# Arm_controller.net
KiCad netlist of a schematic drawn in EAGLE
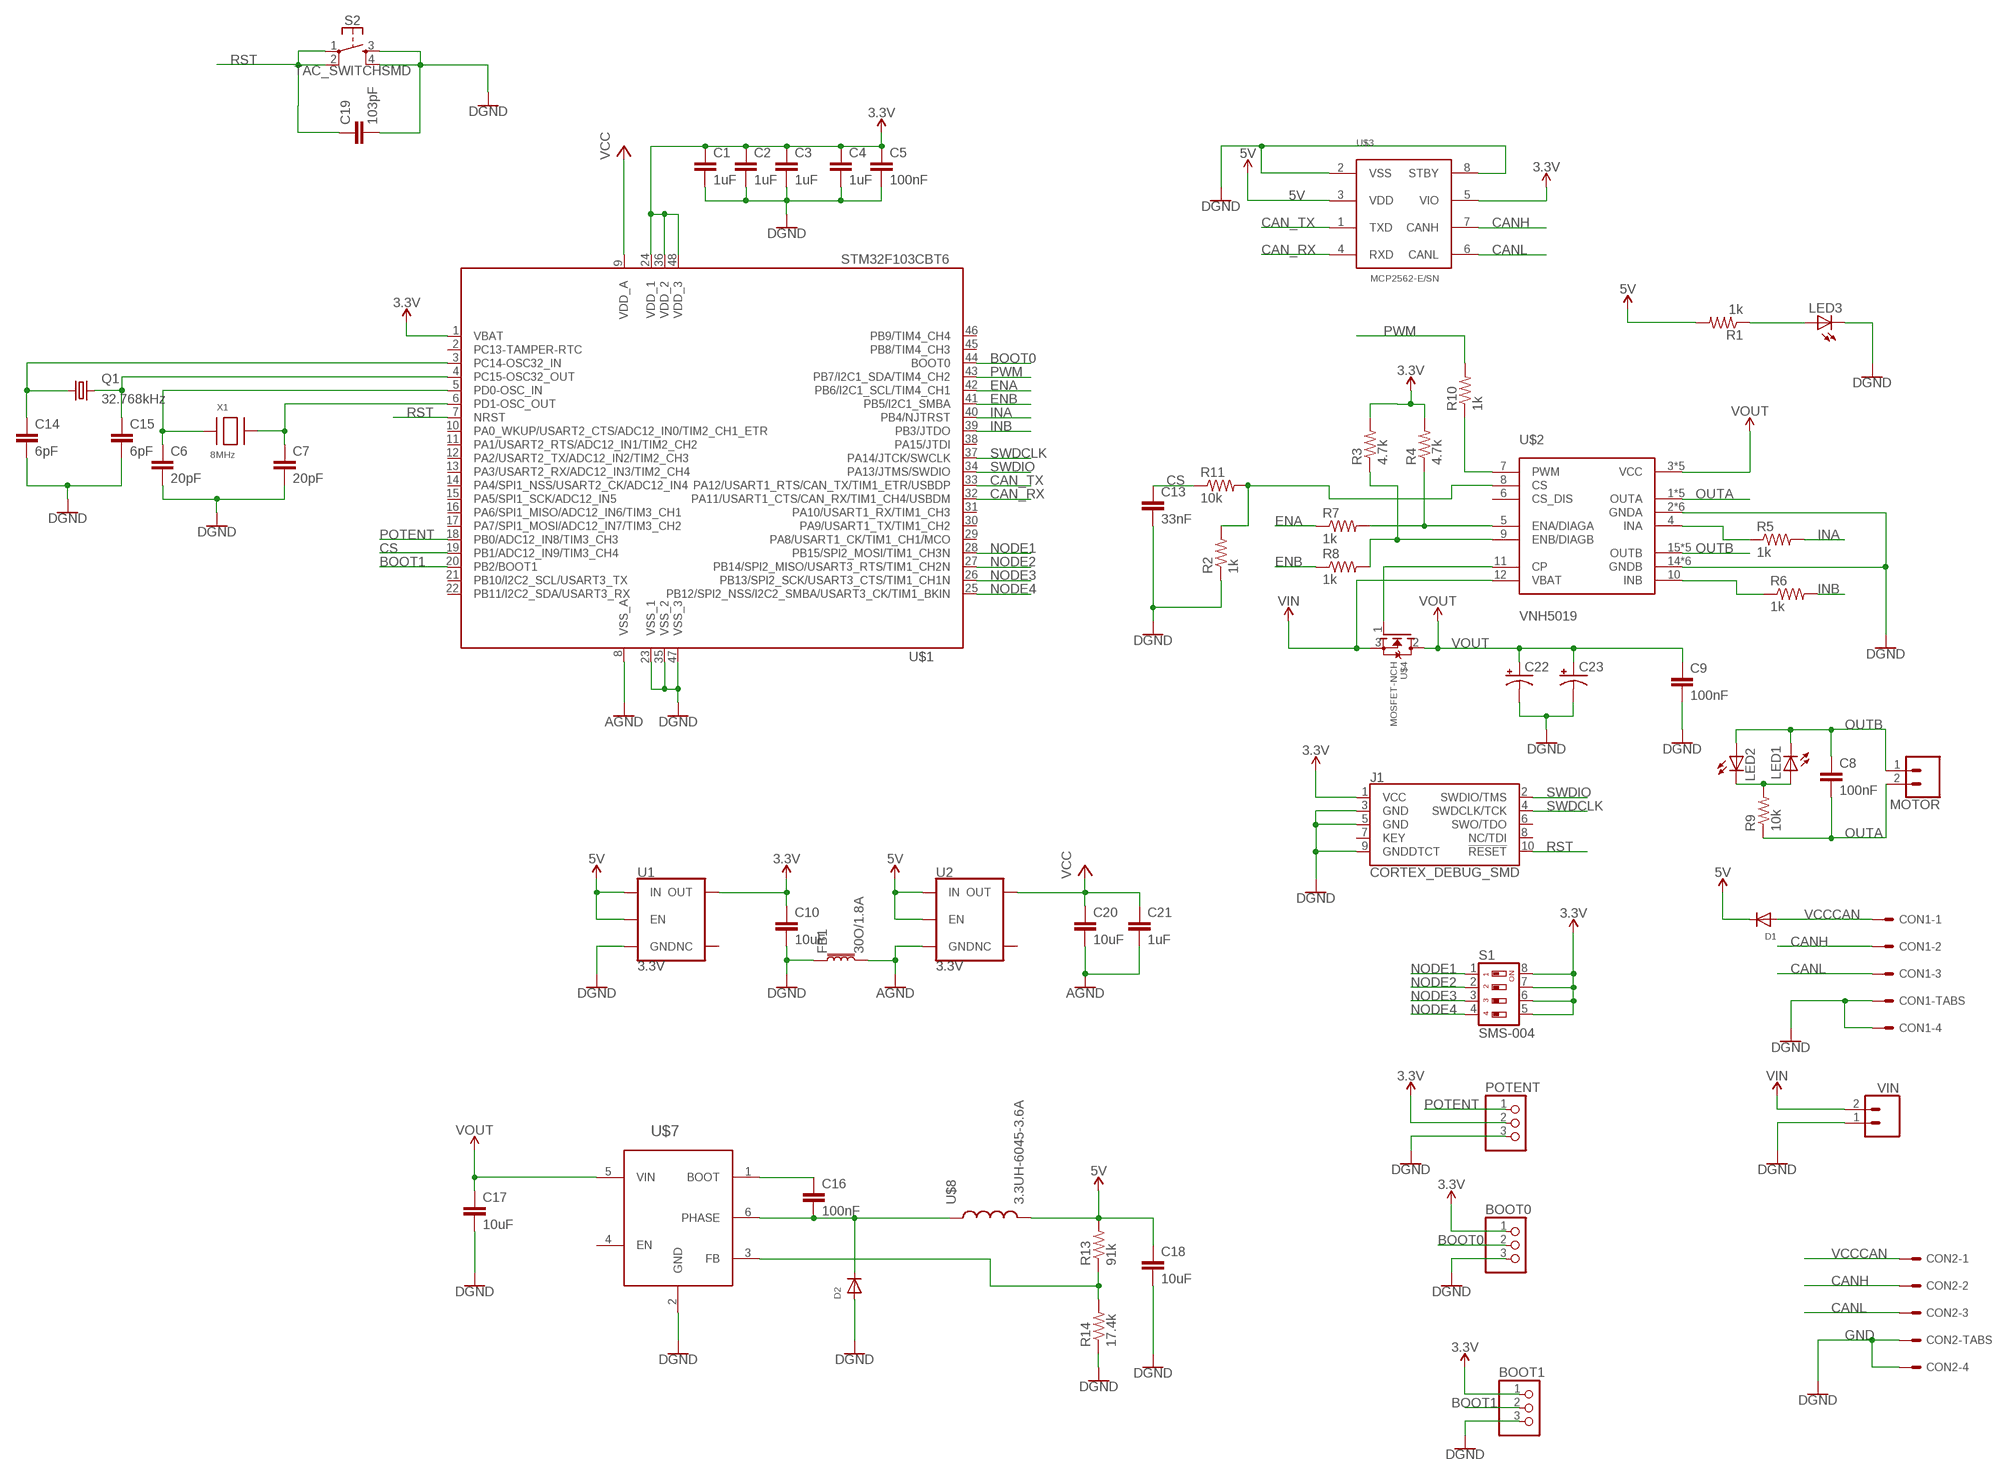
[diagram p0: schematic, sheet 1]

(export (version "E")
  (design (tool "Eeschema 10.0.6"))
  (components
    (comp (ref "BOOT0")
      (value "PINHD-1X3")
      (footprint "eagle-import:1X03")
      (libsource (lib "eagle-import") (part "PINHD-1X3"))
    )
    (comp (ref "BOOT1")
      (value "PINHD-1X3")
      (footprint "eagle-import:1X03")
      (libsource (lib "eagle-import") (part "PINHD-1X3"))
    )
    (comp (ref "C1")
      (value "1uF")
      (footprint "eagle-import:C0805")
      (libsource (lib "eagle-import") (part "C-EUC0805"))
    )
    (comp (ref "C2")
      (value "1uF")
      (footprint "eagle-import:C0805")
      (libsource (lib "eagle-import") (part "C-EUC0805"))
    )
    (comp (ref "C3")
      (value "1uF")
      (footprint "eagle-import:C0805")
      (libsource (lib "eagle-import") (part "C-EUC0805"))
    )
    (comp (ref "C4")
      (value "1uF")
      (footprint "eagle-import:C0805")
      (libsource (lib "eagle-import") (part "C-EUC0805"))
    )
    (comp (ref "C5")
      (value "100nF")
      (footprint "eagle-import:C0805")
      (libsource (lib "eagle-import") (part "C-EUC0805"))
    )
    (comp (ref "C6")
      (value "20pF")
      (footprint "eagle-import:C0805")
      (libsource (lib "eagle-import") (part "C-EUC0805"))
    )
    (comp (ref "C7")
      (value "20pF")
      (footprint "eagle-import:C0805")
      (libsource (lib "eagle-import") (part "C-EUC0805"))
    )
    (comp (ref "C8")
      (value "100nF")
      (footprint "eagle-import:C1206")
      (libsource (lib "eagle-import") (part "resistor_348_C-EUC1206"))
    )
    (comp (ref "C9")
      (value "100nF")
      (footprint "eagle-import:C0805")
      (libsource (lib "eagle-import") (part "C-EUC0805"))
    )
    (comp (ref "C10")
      (value "10uF")
      (footprint "eagle-import:C1206")
      (libsource (lib "eagle-import") (part "resistor_348_C-EUC1206"))
    )
    (comp (ref "C13")
      (value "33nF")
      (footprint "eagle-import:C0805")
      (libsource (lib "eagle-import") (part "C-EUC0805"))
    )
    (comp (ref "C14")
      (value "6pF")
      (footprint "eagle-import:C0805")
      (libsource (lib "eagle-import") (part "C-EUC0805"))
    )
    (comp (ref "C15")
      (value "6pF")
      (footprint "eagle-import:C0805")
      (libsource (lib "eagle-import") (part "C-EUC0805"))
    )
    (comp (ref "C16")
      (value "100nF")
      (footprint "eagle-import:C0805")
      (libsource (lib "eagle-import") (part "resistor_348_C-EUC0805"))
    )
    (comp (ref "C17")
      (value "10uF")
      (footprint "eagle-import:C1206")
      (libsource (lib "eagle-import") (part "resistor_348_C-EUC1206"))
    )
    (comp (ref "C18")
      (value "10uF")
      (footprint "eagle-import:C1206")
      (libsource (lib "eagle-import") (part "C-EUC1206"))
    )
    (comp (ref "C19")
      (value "103pF")
      (footprint "eagle-import:C0805")
      (libsource (lib "eagle-import") (part "C-EUC0805"))
    )
    (comp (ref "C20")
      (value "10uF")
      (footprint "eagle-import:C1206")
      (libsource (lib "eagle-import") (part "resistor_348_C-EUC1206"))
    )
    (comp (ref "C21")
      (value "1uF")
      (footprint "eagle-import:C0805")
      (libsource (lib "eagle-import") (part "C-EUC0805"))
    )
    (comp (ref "C22")
      (value "CPOL-USCT7343")
      (footprint "eagle-import:CT7343")
      (libsource (lib "eagle-import") (part "CPOL-USCT7343"))
    )
    (comp (ref "C23")
      (value "CPOL-USCT7343")
      (footprint "eagle-import:CT7343")
      (libsource (lib "eagle-import") (part "CPOL-USCT7343"))
    )
    (comp (ref "CON1")
      (value "SM04B-GHS-TB")
      (footprint "eagle-import:SM04B-GHS-TB")
      (libsource (lib "eagle-import") (part "SM04B-GHS-TB"))
    )
    (comp (ref "CON2")
      (value "SM04B-GHS-TB")
      (footprint "eagle-import:SM04B-GHS-TB")
      (libsource (lib "eagle-import") (part "SM04B-GHS-TB"))
    )
    (comp (ref "D1")
      (value "DIODESOD-123")
      (footprint "eagle-import:SOD-123")
      (libsource (lib "eagle-import") (part "DIODESOD-123"))
    )
    (comp (ref "D2")
      (value "DIODESOD-123")
      (footprint "eagle-import:SOD-123")
      (libsource (lib "eagle-import") (part "DIODESOD-123"))
    )
    (comp (ref "FB1")
      (value "30O/1.8A")
      (footprint "eagle-import:0603")
      (libsource (lib "eagle-import") (part "FERRITE_BEAD-0603"))
    )
    (comp (ref "J1")
      (value "CORTEX_DEBUG_SMD")
      (footprint "eagle-import:SAMTECH_FTSH-105-01")
      (libsource (lib "eagle-import") (part "CORTEX_DEBUG_SMD"))
    )
    (comp (ref "LED1")
      (value "LEDCHIPLED_0805")
      (footprint "eagle-import:CHIPLED_0805")
      (libsource (lib "eagle-import") (part "LEDCHIPLED_0805"))
    )
    (comp (ref "LED2")
      (value "LEDCHIPLED_0805")
      (footprint "eagle-import:CHIPLED_0805")
      (libsource (lib "eagle-import") (part "LEDCHIPLED_0805"))
    )
    (comp (ref "LED3")
      (value "LEDCHIPLED_0805")
      (footprint "eagle-import:CHIPLED_0805")
      (libsource (lib "eagle-import") (part "LEDCHIPLED_0805"))
    )
    (comp (ref "MOTOR")
      (value "CONN_025MM")
      (footprint "eagle-import:SCREWTERMINAL-5MM-2")
      (libsource (lib "eagle-import") (part "CONN_025MM"))
    )
    (comp (ref "POTENT")
      (value "PINHD-1X3")
      (footprint "eagle-import:1X03")
      (libsource (lib "eagle-import") (part "PINHD-1X3"))
    )
    (comp (ref "Q1")
      (value "32.768kHz")
      (footprint "eagle-import:3.2X1.5")
      (libsource (lib "eagle-import") (part "KX-327"))
    )
    (comp (ref "R1")
      (value "1k")
      (footprint "eagle-import:R0805")
      (libsource (lib "eagle-import") (part "R-US_R0805"))
    )
    (comp (ref "R2")
      (value "1k")
      (footprint "eagle-import:R0805")
      (libsource (lib "eagle-import") (part "R-US_R0805"))
    )
    (comp (ref "R3")
      (value "4.7k")
      (footprint "eagle-import:R0805")
      (libsource (lib "eagle-import") (part "R-US_R0805"))
    )
    (comp (ref "R4")
      (value "4.7k")
      (footprint "eagle-import:R0805")
      (libsource (lib "eagle-import") (part "R-US_R0805"))
    )
    (comp (ref "R5")
      (value "1k")
      (footprint "eagle-import:R0805")
      (libsource (lib "eagle-import") (part "R-US_R0805"))
    )
    (comp (ref "R6")
      (value "1k")
      (footprint "eagle-import:R0805")
      (libsource (lib "eagle-import") (part "R-US_R0805"))
    )
    (comp (ref "R7")
      (value "1k")
      (footprint "eagle-import:R0805")
      (libsource (lib "eagle-import") (part "R-US_R0805"))
    )
    (comp (ref "R8")
      (value "1k")
      (footprint "eagle-import:R0805")
      (libsource (lib "eagle-import") (part "R-US_R0805"))
    )
    (comp (ref "R9")
      (value "10k")
      (footprint "eagle-import:R0805")
      (libsource (lib "eagle-import") (part "R-US_R0805"))
    )
    (comp (ref "R10")
      (value "1k")
      (footprint "eagle-import:R0805")
      (libsource (lib "eagle-import") (part "R-US_R0805"))
    )
    (comp (ref "R11")
      (value "10k")
      (footprint "eagle-import:R0805")
      (libsource (lib "eagle-import") (part "R-US_R0805"))
    )
    (comp (ref "R13")
      (value "91k")
      (footprint "eagle-import:R0805")
      (libsource (lib "eagle-import") (part "R-US_R0805"))
    )
    (comp (ref "R14")
      (value "17.4k")
      (footprint "eagle-import:R0805")
      (libsource (lib "eagle-import") (part "R-US_R0805"))
    )
    (comp (ref "S1")
      (value "SMS-004")
      (footprint "eagle-import:SMS-004")
      (libsource (lib "eagle-import") (part "SMS-004"))
    )
    (comp (ref "S2")
      (value "TAC_SWITCHSMD")
      (footprint "eagle-import:TACTILE_SWITCH_SMD_5.2MM")
      (libsource (lib "eagle-import") (part "MOMENTARY-SWITCH-SPST-2-SMD-5.2MM"))
    )
    (comp (ref "U$1")
      (value "STM32F103CBT6")
      (footprint "eagle-import:STM32_LQFP48")
      (libsource (lib "eagle-import") (part "STM32F103CBT6"))
    )
    (comp (ref "U$2")
      (value "VNH5019")
      (footprint "eagle-import:MULTIPOWERSO-30")
      (libsource (lib "eagle-import") (part "VNH5019"))
    )
    (comp (ref "U$3")
      (value "MCP2562-E/SN")
      (footprint "eagle-import:SOIC8")
      (libsource (lib "eagle-import") (part "MCP2562-E/SN"))
    )
    (comp (ref "U$4")
      (value "MOSFET-NCH")
      (footprint "eagle-import:TO252-3")
      (libsource (lib "eagle-import") (part "MOSFET-NCH"))
    )
    (comp (ref "U$7")
      (value "RT6200")
      (footprint "eagle-import:TSOT23-6")
      (libsource (lib "eagle-import") (part "RT6200"))
    )
    (comp (ref "U$8")
      (value "3.3UH-6045-3.6A")
      (footprint "eagle-import:INDC6161X450")
      (libsource (lib "eagle-import") (part "3.3UH-6045-3.6A"))
    )
    (comp (ref "U1")
      (value "3.3V")
      (footprint "eagle-import:SOT23-5")
      (libsource (lib "eagle-import") (part "V_REG_AP2112K-3.3V"))
    )
    (comp (ref "U2")
      (value "3.3V")
      (footprint "eagle-import:SOT23-5")
      (libsource (lib "eagle-import") (part "V_REG_AP2112K-3.3V"))
    )
    (comp (ref "VIN")
      (value "CONN_025MM")
      (footprint "eagle-import:SCREWTERMINAL-5MM-2")
      (libsource (lib "eagle-import") (part "CONN_025MM"))
    )
    (comp (ref "X1")
      (value "8MHz")
      (footprint "eagle-import:NX5032")
      (libsource (lib "eagle-import") (part "XTALNX5032"))
    )
  )
  (nets
    (net (code "1") (name "/BOOT0") (class "Default")
      (node (ref "BOOT0") (pin "2") (pinfunction "2_2") (pintype "passive"))
      (node (ref "U$1") (pin "44") (pinfunction "BOOT0_44") (pintype "input"))
    )
    (net (code "2") (name "/BOOT1") (class "Default")
      (node (ref "BOOT1") (pin "2") (pinfunction "2_2") (pintype "passive"))
      (node (ref "U$1") (pin "20") (pinfunction "PB2/BOOT1_20") (pintype "bidirectional"))
    )
    (net (code "3") (name "/CANH") (class "Default")
      (node (ref "CON1") (pin "P$2") (pinfunction "S_P$2") (pintype "passive"))
      (node (ref "CON2") (pin "P$2") (pinfunction "S_P$2") (pintype "passive"))
      (node (ref "U$3") (pin "7") (pinfunction "CANH_7") (pintype "bidirectional"))
    )
    (net (code "4") (name "/CANL") (class "Default")
      (node (ref "CON1") (pin "P$3") (pinfunction "S_P$3") (pintype "passive"))
      (node (ref "CON2") (pin "P$3") (pinfunction "S_P$3") (pintype "passive"))
      (node (ref "U$3") (pin "6") (pinfunction "CANL_6") (pintype "bidirectional"))
    )
    (net (code "5") (name "/CAN_RX") (class "Default")
      (node (ref "U$1") (pin "32") (pinfunction "PA11/USART1_CTS/CAN_RX/TIM1_CH4/USBDM_32") (pintype "bidirectional"))
      (node (ref "U$3") (pin "4") (pinfunction "RXD_4") (pintype "bidirectional"))
    )
    (net (code "6") (name "/CAN_TX") (class "Default")
      (node (ref "U$1") (pin "33") (pinfunction "PA12/USART1_RTS/CAN_TX/TIM1_ETR/USBDP_33") (pintype "bidirectional"))
      (node (ref "U$3") (pin "1") (pinfunction "TXD_1") (pintype "bidirectional"))
    )
    (net (code "7") (name "/CS") (class "Default")
      (node (ref "C13") (pin "1") (pinfunction "1_1") (pintype "passive"))
      (node (ref "R11") (pin "1") (pinfunction "1_1") (pintype "passive"))
      (node (ref "U$1") (pin "19") (pinfunction "PB1/ADC12_IN9/TIM3_CH4_19") (pintype "bidirectional"))
    )
    (net (code "8") (name "/ENA") (class "Default")
      (node (ref "R7") (pin "1") (pinfunction "1_1") (pintype "passive"))
      (node (ref "U$1") (pin "42") (pinfunction "PB6/I2C1_SCL/TIM4_CH1_42") (pintype "input"))
    )
    (net (code "9") (name "/ENB") (class "Default")
      (node (ref "R8") (pin "1") (pinfunction "1_1") (pintype "passive"))
      (node (ref "U$1") (pin "41") (pinfunction "PB5/I2C1_SMBA_41") (pintype "input"))
    )
    (net (code "10") (name "/INA") (class "Default")
      (node (ref "R5") (pin "2") (pinfunction "2_2") (pintype "passive"))
      (node (ref "U$1") (pin "40") (pinfunction "PB4/NJTRST_40") (pintype "bidirectional"))
    )
    (net (code "11") (name "/INB") (class "Default")
      (node (ref "R6") (pin "2") (pinfunction "2_2") (pintype "passive"))
      (node (ref "U$1") (pin "39") (pinfunction "PB3/JTDO_39") (pintype "bidirectional"))
    )
    (net (code "12") (name "/NODE1") (class "Default")
      (node (ref "S1") (pin "1") (pinfunction "1_1") (pintype "passive"))
      (node (ref "U$1") (pin "28") (pinfunction "PB15/SPI2_MOSI/TIM1_CH3N_28") (pintype "input"))
    )
    (net (code "13") (name "/NODE2") (class "Default")
      (node (ref "S1") (pin "2") (pinfunction "2_2") (pintype "passive"))
      (node (ref "U$1") (pin "27") (pinfunction "PB14/SPI2_MISO/USART3_RTS/TIM1_CH2N_27") (pintype "input"))
    )
    (net (code "14") (name "/NODE3") (class "Default")
      (node (ref "S1") (pin "3") (pinfunction "3_3") (pintype "passive"))
      (node (ref "U$1") (pin "26") (pinfunction "PB13/SPI2_SCK/USART3_CTS/TIM1_CH1N_26") (pintype "input"))
    )
    (net (code "15") (name "/NODE4") (class "Default")
      (node (ref "S1") (pin "4") (pinfunction "4_4") (pintype "passive"))
      (node (ref "U$1") (pin "25") (pinfunction "PB12/SPI2_NSS/I2C2_SMBA/USART3_CK/TIM1_BKIN_25") (pintype "input"))
    )
    (net (code "16") (name "/OUTA") (class "Default")
      (node (ref "C8") (pin "2") (pinfunction "2_2") (pintype "passive"))
      (node (ref "MOTOR") (pin "2") (pinfunction "2_2") (pintype "passive"))
      (node (ref "R9") (pin "1") (pinfunction "1_1") (pintype "passive"))
      (node (ref "U$2") (pin "1") (pinfunction "OUTA_1") (pintype "bidirectional"))
      (node (ref "U$2") (pin "25") (pinfunction "OUTA_25") (pintype "bidirectional"))
      (node (ref "U$2") (pin "30") (pinfunction "OUTA_30") (pintype "bidirectional"))
      (node (ref "U$2") (pin "OUTA") (pinfunction "OUTA_OUTA") (pintype "bidirectional"))
      (node (ref "U$2") (pin "OUTA@1") (pinfunction "OUTA_OUTA@1") (pintype "bidirectional"))
    )
    (net (code "17") (name "/OUTB") (class "Default")
      (node (ref "C8") (pin "1") (pinfunction "1_1") (pintype "passive"))
      (node (ref "LED1") (pin "C") (pinfunction "C_C") (pintype "passive"))
      (node (ref "LED2") (pin "A") (pinfunction "A_A") (pintype "passive"))
      (node (ref "MOTOR") (pin "1") (pinfunction "1_1") (pintype "passive"))
      (node (ref "U$2") (pin "15") (pinfunction "OUTB_15") (pintype "bidirectional"))
      (node (ref "U$2") (pin "16") (pinfunction "OUTB_16") (pintype "bidirectional"))
      (node (ref "U$2") (pin "21") (pinfunction "OUTB_21") (pintype "bidirectional"))
      (node (ref "U$2") (pin "OUTB") (pinfunction "OUTB_OUTB") (pintype "bidirectional"))
      (node (ref "U$2") (pin "OUTB@1") (pinfunction "OUTB_OUTB@1") (pintype "bidirectional"))
    )
    (net (code "18") (name "/POTENT") (class "Default")
      (node (ref "POTENT") (pin "1") (pinfunction "1_1") (pintype "passive"))
      (node (ref "U$1") (pin "18") (pinfunction "PB0/ADC12_IN8/TIM3_CH3_18") (pintype "bidirectional"))
    )
    (net (code "19") (name "/PWM") (class "Default")
      (node (ref "R10") (pin "2") (pinfunction "2_2") (pintype "passive"))
      (node (ref "U$1") (pin "43") (pinfunction "PB7/I2C1_SDA/TIM4_CH2_43") (pintype "bidirectional"))
    )
    (net (code "20") (name "/RST") (class "Default")
      (node (ref "C19") (pin "1") (pinfunction "1_1") (pintype "passive"))
      (node (ref "J1") (pin "10") (pinfunction "~{RESET}_10") (pintype "bidirectional"))
      (node (ref "S2") (pin "1") (pinfunction "1_1") (pintype "passive"))
      (node (ref "S2") (pin "2") (pinfunction "2_2") (pintype "passive"))
      (node (ref "U$1") (pin "7") (pinfunction "NRST_7") (pintype "input"))
    )
    (net (code "21") (name "/SWDCLK") (class "Default")
      (node (ref "J1") (pin "4") (pinfunction "SWDCLK/TCK_4") (pintype "bidirectional"))
      (node (ref "U$1") (pin "37") (pinfunction "PA14/JTCK/SWCLK_37") (pintype "bidirectional"))
    )
    (net (code "22") (name "/SWDIO") (class "Default")
      (node (ref "J1") (pin "2") (pinfunction "SWDIO/TMS_2") (pintype "bidirectional"))
      (node (ref "U$1") (pin "34") (pinfunction "PA13/JTMS/SWDIO_34") (pintype "bidirectional"))
    )
    (net (code "23") (name "/VCCCAN") (class "Default")
      (node (ref "CON1") (pin "P$1") (pinfunction "S_P$1") (pintype "passive"))
      (node (ref "CON2") (pin "P$1") (pinfunction "S_P$1") (pintype "passive"))
      (node (ref "D1") (pin "A") (pinfunction "A_A") (pintype "passive"))
    )
    (net (code "24") (name "3.3V") (class "Default")
      (node (ref "BOOT0") (pin "1") (pinfunction "1_1") (pintype "passive"))
      (node (ref "BOOT1") (pin "1") (pinfunction "1_1") (pintype "passive"))
      (node (ref "C1") (pin "1") (pinfunction "1_1") (pintype "passive"))
      (node (ref "C10") (pin "1") (pinfunction "1_1") (pintype "passive"))
      (node (ref "C2") (pin "1") (pinfunction "1_1") (pintype "passive"))
      (node (ref "C3") (pin "1") (pinfunction "1_1") (pintype "passive"))
      (node (ref "C4") (pin "1") (pinfunction "1_1") (pintype "passive"))
      (node (ref "C5") (pin "1") (pinfunction "1_1") (pintype "passive"))
      (node (ref "J1") (pin "1") (pinfunction "VCC_1") (pintype "bidirectional"))
      (node (ref "POTENT") (pin "2") (pinfunction "2_2") (pintype "passive"))
      (node (ref "R3") (pin "2") (pinfunction "2_2") (pintype "passive"))
      (node (ref "R4") (pin "2") (pinfunction "2_2") (pintype "passive"))
      (node (ref "S1") (pin "5") (pinfunction "5_5") (pintype "passive"))
      (node (ref "S1") (pin "6") (pinfunction "6_6") (pintype "passive"))
      (node (ref "S1") (pin "7") (pinfunction "7_7") (pintype "passive"))
      (node (ref "S1") (pin "8") (pinfunction "8_8") (pintype "passive"))
      (node (ref "U$1") (pin "1") (pinfunction "VBAT_1") (pintype "power_in"))
      (node (ref "U$1") (pin "24") (pinfunction "VDD_1_24") (pintype "power_in"))
      (node (ref "U$1") (pin "36") (pinfunction "VDD_2_36") (pintype "power_in"))
      (node (ref "U$1") (pin "48") (pinfunction "VDD_3_48") (pintype "power_in"))
      (node (ref "U$3") (pin "5") (pinfunction "VIO_5") (pintype "bidirectional"))
      (node (ref "U1") (pin "5") (pinfunction "OUT_5") (pintype "passive"))
    )
    (net (code "25") (name "5V") (class "Default")
      (node (ref "C18") (pin "1") (pinfunction "1_1") (pintype "passive"))
      (node (ref "D1") (pin "C") (pinfunction "C_C") (pintype "passive"))
      (node (ref "R1") (pin "2") (pinfunction "2_2") (pintype "passive"))
      (node (ref "R13") (pin "2") (pinfunction "2_2") (pintype "passive"))
      (node (ref "U$3") (pin "3") (pinfunction "VDD_3") (pintype "bidirectional"))
      (node (ref "U$8") (pin "2") (pinfunction "2_2") (pintype "passive"))
      (node (ref "U1") (pin "1") (pinfunction "IN_1") (pintype "input"))
      (node (ref "U1") (pin "3") (pinfunction "EN_3") (pintype "input"))
      (node (ref "U2") (pin "1") (pinfunction "IN_1") (pintype "input"))
      (node (ref "U2") (pin "3") (pinfunction "EN_3") (pintype "input"))
    )
    (net (code "26") (name "AGND") (class "Default")
      (node (ref "C20") (pin "2") (pinfunction "2_2") (pintype "passive"))
      (node (ref "C21") (pin "2") (pinfunction "2_2") (pintype "passive"))
      (node (ref "FB1") (pin "2") (pinfunction "2_2") (pintype "passive"))
      (node (ref "U$1") (pin "8") (pinfunction "VSS_A_8") (pintype "power_in"))
      (node (ref "U2") (pin "2") (pinfunction "GND_2") (pintype "input"))
    )
    (net (code "27") (name "DGND") (class "Default")
      (node (ref "BOOT0") (pin "3") (pinfunction "3_3") (pintype "passive"))
      (node (ref "BOOT1") (pin "3") (pinfunction "3_3") (pintype "passive"))
      (node (ref "C1") (pin "2") (pinfunction "2_2") (pintype "passive"))
      (node (ref "C10") (pin "2") (pinfunction "2_2") (pintype "passive"))
      (node (ref "C13") (pin "2") (pinfunction "2_2") (pintype "passive"))
      (node (ref "C14") (pin "2") (pinfunction "2_2") (pintype "passive"))
      (node (ref "C15") (pin "2") (pinfunction "2_2") (pintype "passive"))
      (node (ref "C17") (pin "2") (pinfunction "2_2") (pintype "passive"))
      (node (ref "C18") (pin "2") (pinfunction "2_2") (pintype "passive"))
      (node (ref "C19") (pin "2") (pinfunction "2_2") (pintype "passive"))
      (node (ref "C2") (pin "2") (pinfunction "2_2") (pintype "passive"))
      (node (ref "C22") (pin "-") (pinfunction "-_-") (pintype "passive"))
      (node (ref "C23") (pin "-") (pinfunction "-_-") (pintype "passive"))
      (node (ref "C3") (pin "2") (pinfunction "2_2") (pintype "passive"))
      (node (ref "C4") (pin "2") (pinfunction "2_2") (pintype "passive"))
      (node (ref "C5") (pin "2") (pinfunction "2_2") (pintype "passive"))
      (node (ref "C6") (pin "2") (pinfunction "2_2") (pintype "passive"))
      (node (ref "C7") (pin "2") (pinfunction "2_2") (pintype "passive"))
      (node (ref "C9") (pin "2") (pinfunction "2_2") (pintype "passive"))
      (node (ref "CON1") (pin "P$4") (pinfunction "S_P$4") (pintype "passive"))
      (node (ref "CON1") (pin "P$5") (pinfunction "S_P$5") (pintype "passive"))
      (node (ref "CON1") (pin "P$6") (pinfunction "S_P$6") (pintype "passive"))
      (node (ref "CON2") (pin "P$4") (pinfunction "S_P$4") (pintype "passive"))
      (node (ref "CON2") (pin "P$5") (pinfunction "S_P$5") (pintype "passive"))
      (node (ref "CON2") (pin "P$6") (pinfunction "S_P$6") (pintype "passive"))
      (node (ref "D2") (pin "A") (pinfunction "A_A") (pintype "passive"))
      (node (ref "FB1") (pin "1") (pinfunction "1_1") (pintype "passive"))
      (node (ref "J1") (pin "3") (pinfunction "GND_3") (pintype "bidirectional"))
      (node (ref "J1") (pin "5") (pinfunction "GND_5") (pintype "bidirectional"))
      (node (ref "J1") (pin "9") (pinfunction "GNDDTCT_9") (pintype "bidirectional"))
      (node (ref "LED3") (pin "C") (pinfunction "C_C") (pintype "passive"))
      (node (ref "POTENT") (pin "3") (pinfunction "3_3") (pintype "passive"))
      (node (ref "R14") (pin "1") (pinfunction "1_1") (pintype "passive"))
      (node (ref "R2") (pin "1") (pinfunction "1_1") (pintype "passive"))
      (node (ref "S2") (pin "3") (pinfunction "3_3") (pintype "passive"))
      (node (ref "S2") (pin "4") (pinfunction "4_4") (pintype "passive"))
      (node (ref "U$1") (pin "23") (pinfunction "VSS_1_23") (pintype "power_in"))
      (node (ref "U$1") (pin "35") (pinfunction "VSS_2_35") (pintype "power_in"))
      (node (ref "U$1") (pin "47") (pinfunction "VSS_3_47") (pintype "power_in"))
      (node (ref "U$2") (pin "14") (pinfunction "GNDB_14") (pintype "bidirectional"))
      (node (ref "U$2") (pin "17") (pinfunction "GNDB_17") (pintype "bidirectional"))
      (node (ref "U$2") (pin "18") (pinfunction "GNDB_18") (pintype "bidirectional"))
      (node (ref "U$2") (pin "19") (pinfunction "GNDB_19") (pintype "bidirectional"))
      (node (ref "U$2") (pin "2") (pinfunction "GNDA_2") (pintype "bidirectional"))
      (node (ref "U$2") (pin "20") (pinfunction "GNDB_20") (pintype "bidirectional"))
      (node (ref "U$2") (pin "22") (pinfunction "GNDA_22") (pintype "bidirectional"))
      (node (ref "U$2") (pin "24") (pinfunction "GNDB_24") (pintype "bidirectional"))
      (node (ref "U$2") (pin "26") (pinfunction "GNDA_26") (pintype "bidirectional"))
      (node (ref "U$2") (pin "27") (pinfunction "GNDA_27") (pintype "bidirectional"))
      (node (ref "U$2") (pin "28") (pinfunction "GNDA_28") (pintype "bidirectional"))
      (node (ref "U$2") (pin "29") (pinfunction "GNDA_29") (pintype "bidirectional"))
      (node (ref "U$3") (pin "2") (pinfunction "VSS_2") (pintype "bidirectional"))
      (node (ref "U$3") (pin "8") (pinfunction "STBY_8") (pintype "bidirectional"))
      (node (ref "U$7") (pin "2") (pinfunction "GND_2") (pintype "power_in"))
      (node (ref "U1") (pin "2") (pinfunction "GND_2") (pintype "input"))
      (node (ref "VIN") (pin "1") (pinfunction "1_1") (pintype "passive"))
    )
    (net (code "28") (name "Net-(LED1-PadA)") (class "Default")
      (node (ref "LED1") (pin "A") (pinfunction "A_A") (pintype "passive"))
      (node (ref "LED2") (pin "C") (pinfunction "C_C") (pintype "passive"))
      (node (ref "R9") (pin "2") (pinfunction "2_2") (pintype "passive"))
    )
    (net (code "29") (name "Net-(LED3-PadA)") (class "Default")
      (node (ref "LED3") (pin "A") (pinfunction "A_A") (pintype "passive"))
      (node (ref "R1") (pin "1") (pinfunction "1_1") (pintype "passive"))
    )
    (net (code "30") (name "Net-(U$1-PC14-OSC32_IN)") (class "Default")
      (node (ref "C14") (pin "1") (pinfunction "1_1") (pintype "passive"))
      (node (ref "Q1") (pin "1") (pinfunction "1_1") (pintype "passive"))
      (node (ref "U$1") (pin "3") (pinfunction "PC14-OSC32_IN_3") (pintype "input"))
    )
    (net (code "31") (name "Net-(U$1-PC15-OSC32_OUT)") (class "Default")
      (node (ref "C15") (pin "1") (pinfunction "1_1") (pintype "passive"))
      (node (ref "Q1") (pin "2") (pinfunction "2_2") (pintype "passive"))
      (node (ref "U$1") (pin "4") (pinfunction "PC15-OSC32_OUT_4") (pintype "input"))
    )
    (net (code "32") (name "Net-(U$1-PD0-OSC_IN)") (class "Default")
      (node (ref "C6") (pin "1") (pinfunction "1_1") (pintype "passive"))
      (node (ref "U$1") (pin "5") (pinfunction "PD0-OSC_IN_5") (pintype "input"))
      (node (ref "X1") (pin "P$1") (pinfunction "P$1_P$1") (pintype "bidirectional"))
    )
    (net (code "33") (name "Net-(U$1-PD1-OSC_OUT)") (class "Default")
      (node (ref "C7") (pin "1") (pinfunction "1_1") (pintype "passive"))
      (node (ref "U$1") (pin "6") (pinfunction "PD1-OSC_OUT_6") (pintype "input"))
      (node (ref "X1") (pin "P$2") (pinfunction "P$2_P$2") (pintype "bidirectional"))
    )
    (net (code "34") (name "Net-(U$2-CP)") (class "Default")
      (node (ref "U$2") (pin "11") (pinfunction "CP_11") (pintype "bidirectional"))
      (node (ref "U$4") (pin "1") (pinfunction "G_1") (pintype "bidirectional"))
    )
    (net (code "35") (name "Net-(U$2-CS)") (class "Default")
      (node (ref "R11") (pin "2") (pinfunction "2_2") (pintype "passive"))
      (node (ref "R2") (pin "2") (pinfunction "2_2") (pintype "passive"))
      (node (ref "U$2") (pin "8") (pinfunction "CS_8") (pintype "bidirectional"))
    )
    (net (code "36") (name "Net-(U$2-ENA{slash}DIAGA)") (class "Default")
      (node (ref "R4") (pin "1") (pinfunction "1_1") (pintype "passive"))
      (node (ref "R7") (pin "2") (pinfunction "2_2") (pintype "passive"))
      (node (ref "U$2") (pin "5") (pinfunction "ENA/DIAGA_5") (pintype "bidirectional"))
    )
    (net (code "37") (name "Net-(U$2-ENB{slash}DIAGB)") (class "Default")
      (node (ref "R3") (pin "1") (pinfunction "1_1") (pintype "passive"))
      (node (ref "R8") (pin "2") (pinfunction "2_2") (pintype "passive"))
      (node (ref "U$2") (pin "9") (pinfunction "ENB/DIAGB_9") (pintype "bidirectional"))
    )
    (net (code "38") (name "Net-(U$2-INA)") (class "Default")
      (node (ref "R5") (pin "1") (pinfunction "1_1") (pintype "passive"))
      (node (ref "U$2") (pin "4") (pinfunction "INA_4") (pintype "bidirectional"))
    )
    (net (code "39") (name "Net-(U$2-INB)") (class "Default")
      (node (ref "R6") (pin "1") (pinfunction "1_1") (pintype "passive"))
      (node (ref "U$2") (pin "10") (pinfunction "INB_10") (pintype "bidirectional"))
    )
    (net (code "40") (name "Net-(U$2-PWM)") (class "Default")
      (node (ref "R10") (pin "1") (pinfunction "1_1") (pintype "passive"))
      (node (ref "U$2") (pin "7") (pinfunction "PWM_7") (pintype "bidirectional"))
    )
    (net (code "41") (name "Net-(U$7-BOOT)") (class "Default")
      (node (ref "C16") (pin "1") (pinfunction "1_1") (pintype "passive"))
      (node (ref "U$7") (pin "1") (pinfunction "BOOT_1") (pintype "bidirectional"))
    )
    (net (code "42") (name "Net-(U$7-FB)") (class "Default")
      (node (ref "R13") (pin "1") (pinfunction "1_1") (pintype "passive"))
      (node (ref "R14") (pin "2") (pinfunction "2_2") (pintype "passive"))
      (node (ref "U$7") (pin "3") (pinfunction "FB_3") (pintype "bidirectional"))
    )
    (net (code "43") (name "Net-(U$7-PHASE)") (class "Default")
      (node (ref "C16") (pin "2") (pinfunction "2_2") (pintype "passive"))
      (node (ref "D2") (pin "C") (pinfunction "C_C") (pintype "passive"))
      (node (ref "U$7") (pin "6") (pinfunction "PHASE_6") (pintype "power_in"))
      (node (ref "U$8") (pin "1") (pinfunction "1_1") (pintype "passive"))
    )
    (net (code "44") (name "VCC") (class "Default")
      (node (ref "C20") (pin "1") (pinfunction "1_1") (pintype "passive"))
      (node (ref "C21") (pin "1") (pinfunction "1_1") (pintype "passive"))
      (node (ref "U$1") (pin "9") (pinfunction "VDD_A_9") (pintype "power_in"))
      (node (ref "U2") (pin "5") (pinfunction "OUT_5") (pintype "passive"))
    )
    (net (code "45") (name "VIN") (class "Default")
      (node (ref "U$2") (pin "12") (pinfunction "VBAT_12") (pintype "bidirectional"))
      (node (ref "U$4") (pin "3") (pinfunction "S_3") (pintype "bidirectional"))
      (node (ref "VIN") (pin "2") (pinfunction "2_2") (pintype "passive"))
    )
    (net (code "46") (name "VOUT") (class "Default")
      (node (ref "C17") (pin "1") (pinfunction "1_1") (pintype "passive"))
      (node (ref "C22") (pin "+") (pinfunction "+_+") (pintype "passive"))
      (node (ref "C23") (pin "+") (pinfunction "+_+") (pintype "passive"))
      (node (ref "C9") (pin "1") (pinfunction "1_1") (pintype "passive"))
      (node (ref "U$2") (pin "13") (pinfunction "VCC_13") (pintype "bidirectional"))
      (node (ref "U$2") (pin "23") (pinfunction "VCC_23") (pintype "bidirectional"))
      (node (ref "U$2") (pin "3") (pinfunction "VCC_3") (pintype "bidirectional"))
      (node (ref "U$2") (pin "VCC") (pinfunction "VCC_VCC") (pintype "bidirectional"))
      (node (ref "U$2") (pin "VCC@1") (pinfunction "VCC_VCC@1") (pintype "bidirectional"))
      (node (ref "U$4") (pin "2") (pinfunction "D_2") (pintype "bidirectional"))
      (node (ref "U$7") (pin "5") (pinfunction "VIN_5") (pintype "power_in"))
    )
    (net (code "47") (name "unconnected-(J1-KEY-Pad7)") (class "Default")
      (node (ref "J1") (pin "7") (pinfunction "KEY_7") (pintype "bidirectional"))
    )
    (net (code "48") (name "unconnected-(J1-NC{slash}TDI-Pad8)") (class "Default")
      (node (ref "J1") (pin "8") (pinfunction "NC/TDI_8") (pintype "bidirectional"))
    )
    (net (code "49") (name "unconnected-(J1-SWO{slash}TDO-Pad6)") (class "Default")
      (node (ref "J1") (pin "6") (pinfunction "SWO/TDO_6") (pintype "bidirectional"))
    )
    (net (code "50") (name "unconnected-(U$1-PA0_WKUP{slash}USART2_CTS{slash}ADC12_IN0{slash}TIM2_CH1_ETR-Pad10)") (class "Default")
      (node (ref "U$1") (pin "10") (pinfunction "PA0_WKUP/USART2_CTS/ADC12_IN0/TIM2_CH1_ETR_10") (pintype "bidirectional"))
    )
    (net (code "51") (name "unconnected-(U$1-PA1{slash}USART2_RTS{slash}ADC12_IN1{slash}TIM2_CH2-Pad11)") (class "Default")
      (node (ref "U$1") (pin "11") (pinfunction "PA1/USART2_RTS/ADC12_IN1/TIM2_CH2_11") (pintype "bidirectional"))
    )
    (net (code "52") (name "unconnected-(U$1-PA2{slash}USART2_TX{slash}ADC12_IN2{slash}TIM2_CH3-Pad12)") (class "Default")
      (node (ref "U$1") (pin "12") (pinfunction "PA2/USART2_TX/ADC12_IN2/TIM2_CH3_12") (pintype "bidirectional"))
    )
    (net (code "53") (name "unconnected-(U$1-PA3{slash}USART2_RX{slash}ADC12_IN3{slash}TIM2_CH4-Pad13)") (class "Default")
      (node (ref "U$1") (pin "13") (pinfunction "PA3/USART2_RX/ADC12_IN3/TIM2_CH4_13") (pintype "bidirectional"))
    )
    (net (code "54") (name "unconnected-(U$1-PA4{slash}SPI1_NSS{slash}USART2_CK{slash}ADC12_IN4-Pad14)") (class "Default")
      (node (ref "U$1") (pin "14") (pinfunction "PA4/SPI1_NSS/USART2_CK/ADC12_IN4_14") (pintype "bidirectional"))
    )
    (net (code "55") (name "unconnected-(U$1-PA5{slash}SPI1_SCK{slash}ADC12_IN5-Pad15)") (class "Default")
      (node (ref "U$1") (pin "15") (pinfunction "PA5/SPI1_SCK/ADC12_IN5_15") (pintype "bidirectional"))
    )
    (net (code "56") (name "unconnected-(U$1-PA6{slash}SPI1_MISO{slash}ADC12_IN6{slash}TIM3_CH1-Pad16)") (class "Default")
      (node (ref "U$1") (pin "16") (pinfunction "PA6/SPI1_MISO/ADC12_IN6/TIM3_CH1_16") (pintype "bidirectional"))
    )
    (net (code "57") (name "unconnected-(U$1-PA7{slash}SPI1_MOSI{slash}ADC12_IN7{slash}TIM3_CH2-Pad17)") (class "Default")
      (node (ref "U$1") (pin "17") (pinfunction "PA7/SPI1_MOSI/ADC12_IN7/TIM3_CH2_17") (pintype "bidirectional"))
    )
    (net (code "58") (name "unconnected-(U$1-PA8{slash}USART1_CK{slash}TIM1_CH1{slash}MCO-Pad29)") (class "Default")
      (node (ref "U$1") (pin "29") (pinfunction "PA8/USART1_CK/TIM1_CH1/MCO_29") (pintype "bidirectional"))
    )
    (net (code "59") (name "unconnected-(U$1-PA9{slash}USART1_TX{slash}TIM1_CH2-Pad30)") (class "Default")
      (node (ref "U$1") (pin "30") (pinfunction "PA9/USART1_TX/TIM1_CH2_30") (pintype "input"))
    )
    (net (code "60") (name "unconnected-(U$1-PA10{slash}USART1_RX{slash}TIM1_CH3-Pad31)") (class "Default")
      (node (ref "U$1") (pin "31") (pinfunction "PA10/USART1_RX/TIM1_CH3_31") (pintype "bidirectional"))
    )
    (net (code "61") (name "unconnected-(U$1-PA15{slash}JTDI-Pad38)") (class "Default")
      (node (ref "U$1") (pin "38") (pinfunction "PA15/JTDI_38") (pintype "bidirectional"))
    )
    (net (code "62") (name "unconnected-(U$1-PB8{slash}TIM4_CH3-Pad45)") (class "Default")
      (node (ref "U$1") (pin "45") (pinfunction "PB8/TIM4_CH3_45") (pintype "bidirectional"))
    )
    (net (code "63") (name "unconnected-(U$1-PB9{slash}TIM4_CH4-Pad46)") (class "Default")
      (node (ref "U$1") (pin "46") (pinfunction "PB9/TIM4_CH4_46") (pintype "input"))
    )
    (net (code "64") (name "unconnected-(U$1-PB10{slash}I2C2_SCL{slash}USART3_TX-Pad21)") (class "Default")
      (node (ref "U$1") (pin "21") (pinfunction "PB10/I2C2_SCL/USART3_TX_21") (pintype "input"))
    )
    (net (code "65") (name "unconnected-(U$1-PB11{slash}I2C2_SDA{slash}USART3_RX-Pad22)") (class "Default")
      (node (ref "U$1") (pin "22") (pinfunction "PB11/I2C2_SDA/USART3_RX_22") (pintype "input"))
    )
    (net (code "66") (name "unconnected-(U$1-PC13-TAMPER-RTC-Pad2)") (class "Default")
      (node (ref "U$1") (pin "2") (pinfunction "PC13-TAMPER-RTC_2") (pintype "input"))
    )
    (net (code "67") (name "unconnected-(U$2-CS_DIS-Pad6)") (class "Default")
      (node (ref "U$2") (pin "6") (pinfunction "CS_DIS_6") (pintype "bidirectional"))
    )
    (net (code "68") (name "unconnected-(U$7-EN-Pad4)") (class "Default")
      (node (ref "U$7") (pin "4") (pinfunction "EN_4") (pintype "bidirectional"))
    )
    (net (code "69") (name "unconnected-(U1-NC-Pad4)") (class "Default")
      (node (ref "U1") (pin "4") (pinfunction "NC_4") (pintype "no_connect"))
    )
    (net (code "70") (name "unconnected-(U2-NC-Pad4)") (class "Default")
      (node (ref "U2") (pin "4") (pinfunction "NC_4") (pintype "no_connect"))
    )
  )
)
